# scard_serial.net
KiCad netlist of a schematic drawn in EAGLE
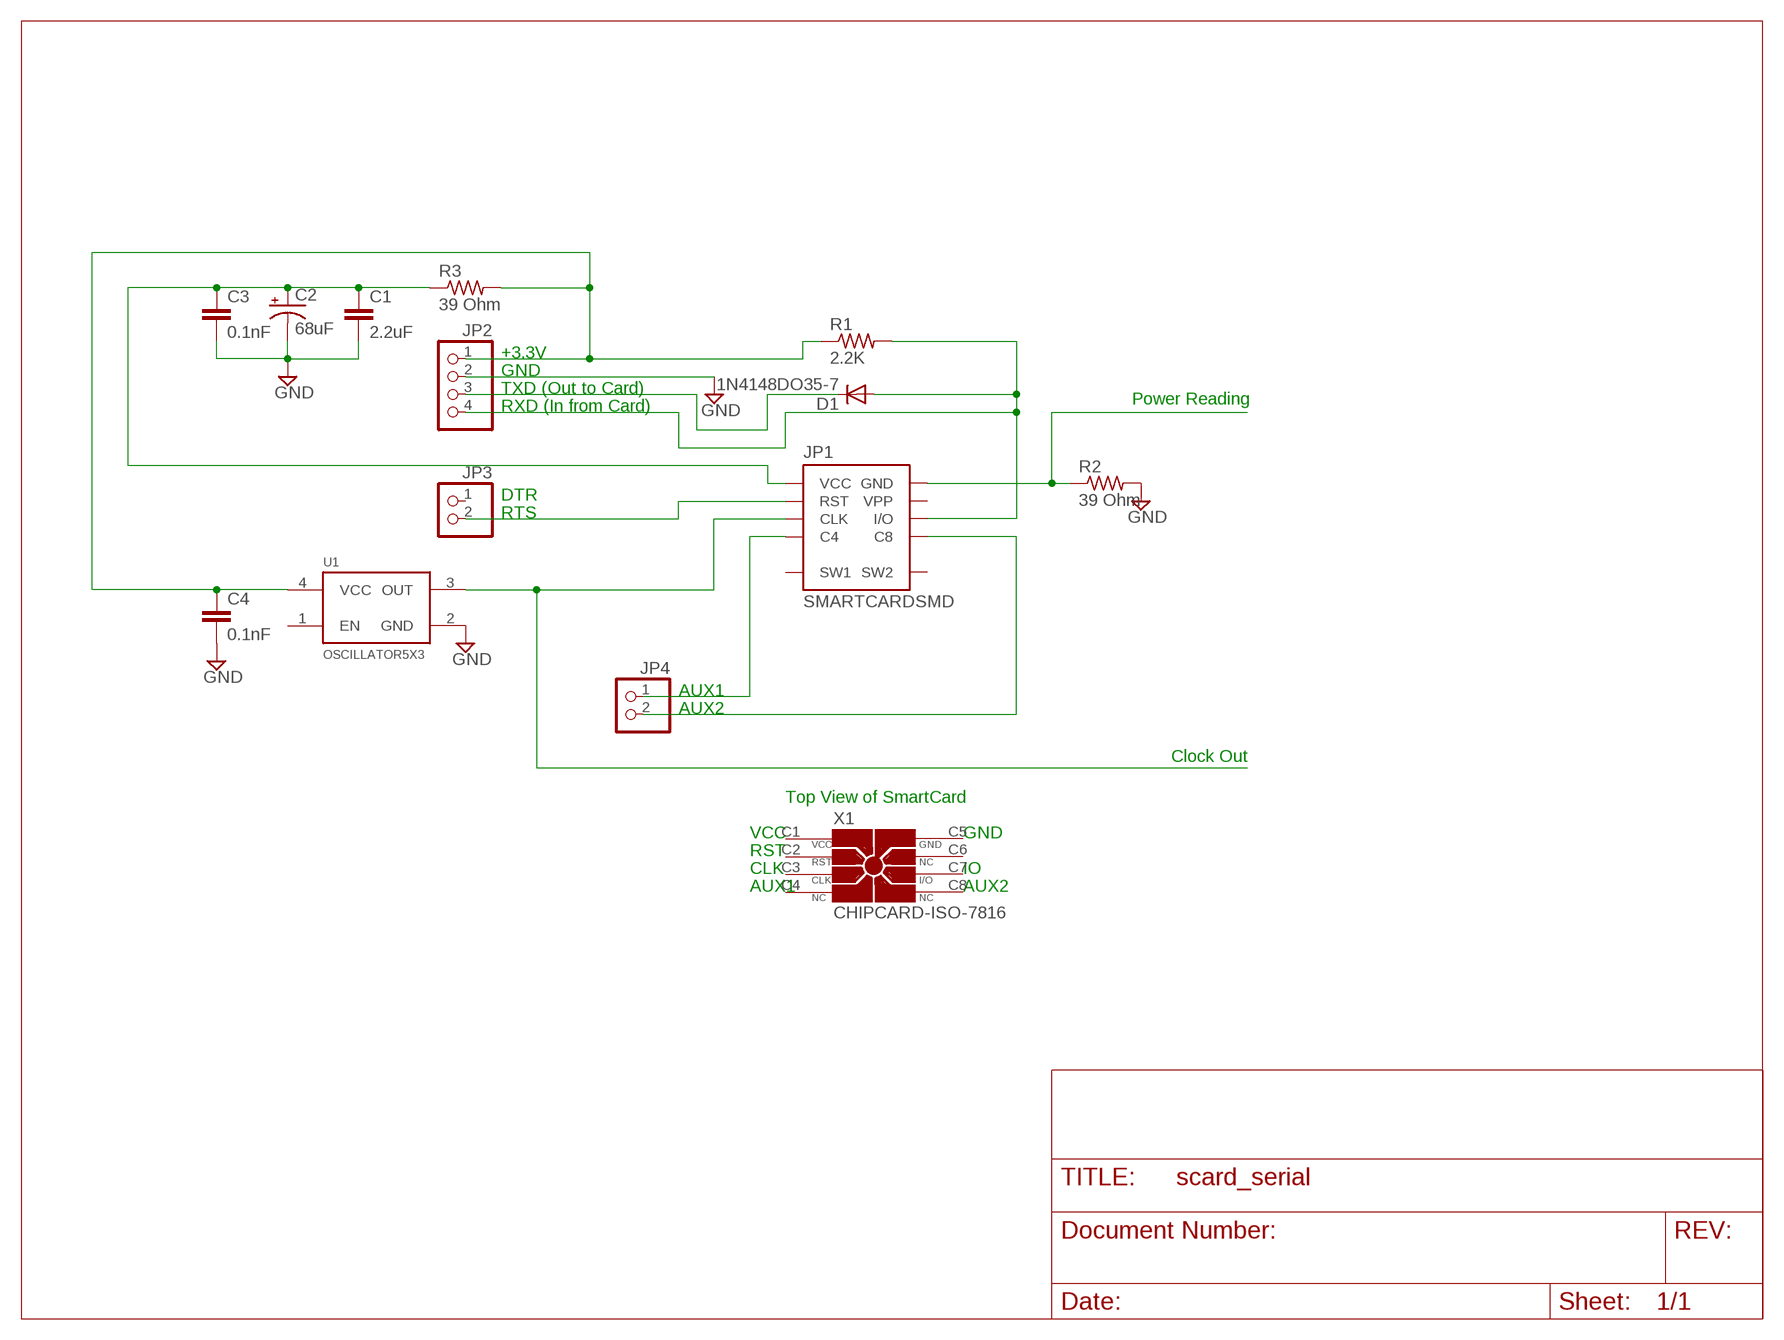
[diagram p0: schematic, sheet 1]

(export (version "E")
  (design (tool "Eeschema 10.0.6"))
  (components
    (comp (ref "C1")
      (value "2.2uF")
      (footprint "eagle-import:C0805")
      (libsource (lib "eagle-import") (part "C-EUC0805"))
    )
    (comp (ref "C2")
      (value "68uF")
      (footprint "eagle-import:139CLL-2W")
      (libsource (lib "eagle-import") (part "CPOL-US139CLL-2W"))
    )
    (comp (ref "C3")
      (value "0.1nF")
      (footprint "eagle-import:C0805")
      (libsource (lib "eagle-import") (part "C-EUC0805"))
    )
    (comp (ref "C4")
      (value "0.1nF")
      (footprint "eagle-import:C0805")
      (libsource (lib "eagle-import") (part "C-EUC0805"))
    )
    (comp (ref "D1")
      (value "1N4148DO35-7")
      (footprint "eagle-import:DO35-7")
      (libsource (lib "eagle-import") (part "1N4148DO35-7"))
    )
    (comp (ref "JP1")
      (value "SMARTCARDSMD")
      (footprint "eagle-import:SMARTCARD")
      (libsource (lib "eagle-import") (part "SMARTCARDSMD"))
    )
    (comp (ref "JP2")
      (value "PINHD-1X4/90")
      (footprint "eagle-import:1X04_90")
      (libsource (lib "eagle-import") (part "PINHD-1X4/90"))
    )
    (comp (ref "JP3")
      (value "PINHD-1X2/90")
      (footprint "eagle-import:1X02_90")
      (libsource (lib "eagle-import") (part "PINHD-1X2/90"))
    )
    (comp (ref "JP4")
      (value "PINHD-1X2/90")
      (footprint "eagle-import:1X02_90")
      (libsource (lib "eagle-import") (part "PINHD-1X2/90"))
    )
    (comp (ref "R1")
      (value "2.2K")
      (footprint "eagle-import:M0805")
      (libsource (lib "eagle-import") (part "R-US_M0805"))
    )
    (comp (ref "R2")
      (value "39 Ohm")
      (footprint "eagle-import:M0805")
      (libsource (lib "eagle-import") (part "R-US_M0805"))
    )
    (comp (ref "R3")
      (value "39 Ohm")
      (footprint "eagle-import:M0805")
      (libsource (lib "eagle-import") (part "R-US_M0805"))
    )
    (comp (ref "U1")
      (value "OSCILLATOR5X3")
      (footprint "eagle-import:CRYSTAL-SMD-5X3")
      (libsource (lib "eagle-import") (part "OSCILLATOR5X3"))
    )
    (comp (ref "X1")
      (value "CHIPCARD-ISO-7816")
      (footprint "eagle-import:ISO7816")
      (libsource (lib "eagle-import") (part "CHIPCARD-ISO-7816"))
    )
  )
  (nets
    (net (code "1") (name "GND") (class "Default")
      (node (ref "C1") (pin "2") (pinfunction "2_2") (pintype "passive"))
      (node (ref "C2") (pin "-") (pinfunction "-_-") (pintype "passive"))
      (node (ref "C3") (pin "2") (pinfunction "2_2") (pintype "passive"))
      (node (ref "C4") (pin "2") (pinfunction "2_2") (pintype "passive"))
      (node (ref "JP2") (pin "2") (pinfunction "2_2") (pintype "passive"))
      (node (ref "R2") (pin "2") (pinfunction "2_2") (pintype "passive"))
      (node (ref "U1") (pin "2") (pinfunction "GND_2") (pintype "bidirectional"))
    )
    (net (code "2") (name "Net-(D1-PadC)") (class "Default")
      (node (ref "D1") (pin "C") (pinfunction "C_C") (pintype "passive"))
      (node (ref "JP2") (pin "3") (pinfunction "3_3") (pintype "passive"))
    )
    (net (code "3") (name "Net-(JP1-CLK)") (class "Default")
      (node (ref "JP1") (pin "C3") (pinfunction "CLK_C3") (pintype "bidirectional"))
      (node (ref "U1") (pin "3") (pinfunction "OUT_3") (pintype "bidirectional"))
    )
    (net (code "4") (name "Net-(JP1-GND)") (class "Default")
      (node (ref "JP1") (pin "C5") (pinfunction "GND_C5") (pintype "bidirectional"))
      (node (ref "R2") (pin "1") (pinfunction "1_1") (pintype "passive"))
    )
    (net (code "5") (name "Net-(JP1-I{slash}O)") (class "Default")
      (node (ref "D1") (pin "A") (pinfunction "A_A") (pintype "passive"))
      (node (ref "JP1") (pin "C7") (pinfunction "I/O_C7") (pintype "bidirectional"))
      (node (ref "JP2") (pin "4") (pinfunction "4_4") (pintype "passive"))
      (node (ref "R1") (pin "2") (pinfunction "2_2") (pintype "passive"))
    )
    (net (code "6") (name "Net-(JP1-PadC4)") (class "Default")
      (node (ref "JP1") (pin "C4") (pinfunction "C4_C4") (pintype "bidirectional"))
      (node (ref "JP4") (pin "1") (pinfunction "1_1") (pintype "passive"))
    )
    (net (code "7") (name "Net-(JP1-PadC8)") (class "Default")
      (node (ref "JP1") (pin "C8") (pinfunction "C8_C8") (pintype "bidirectional"))
      (node (ref "JP4") (pin "2") (pinfunction "2_2") (pintype "passive"))
    )
    (net (code "8") (name "Net-(JP1-RST)") (class "Default")
      (node (ref "JP1") (pin "C2") (pinfunction "RST_C2") (pintype "bidirectional"))
      (node (ref "JP3") (pin "2") (pinfunction "2_2") (pintype "passive"))
    )
    (net (code "9") (name "Net-(JP1-VCC)") (class "Default")
      (node (ref "C1") (pin "1") (pinfunction "1_1") (pintype "passive"))
      (node (ref "C2") (pin "+") (pinfunction "+_+") (pintype "passive"))
      (node (ref "C3") (pin "1") (pinfunction "1_1") (pintype "passive"))
      (node (ref "JP1") (pin "C1") (pinfunction "VCC_C1") (pintype "bidirectional"))
      (node (ref "R3") (pin "1") (pinfunction "1_1") (pintype "passive"))
    )
    (net (code "10") (name "Net-(U1-VCC)") (class "Default")
      (node (ref "C4") (pin "1") (pinfunction "1_1") (pintype "passive"))
      (node (ref "JP2") (pin "1") (pinfunction "1_1") (pintype "passive"))
      (node (ref "R1") (pin "1") (pinfunction "1_1") (pintype "passive"))
      (node (ref "R3") (pin "2") (pinfunction "2_2") (pintype "passive"))
      (node (ref "U1") (pin "4") (pinfunction "VCC_4") (pintype "bidirectional"))
    )
    (net (code "11") (name "unconnected-(JP1-SW1-PadP1)") (class "Default")
      (node (ref "JP1") (pin "P1") (pinfunction "SW1_P1") (pintype "bidirectional"))
    )
    (net (code "12") (name "unconnected-(JP1-SW2-PadP2)") (class "Default")
      (node (ref "JP1") (pin "P2") (pinfunction "SW2_P2") (pintype "bidirectional"))
    )
    (net (code "13") (name "unconnected-(JP1-VPP-PadC6)") (class "Default")
      (node (ref "JP1") (pin "C6") (pinfunction "VPP_C6") (pintype "bidirectional"))
    )
    (net (code "14") (name "unconnected-(JP3-Pad1)") (class "Default")
      (node (ref "JP3") (pin "1") (pinfunction "1_1") (pintype "passive"))
    )
    (net (code "15") (name "unconnected-(U1-EN-Pad1)") (class "Default")
      (node (ref "U1") (pin "1") (pinfunction "EN_1") (pintype "bidirectional"))
    )
    (net (code "16") (name "unconnected-(X1-CLK-PadC3)") (class "Default")
      (node (ref "X1") (pin "C3") (pinfunction "CLK_C3") (pintype "passive"))
    )
    (net (code "17") (name "unconnected-(X1-GND-PadC5)") (class "Default")
      (node (ref "X1") (pin "C5") (pinfunction "GND_C5") (pintype "passive"))
    )
    (net (code "18") (name "unconnected-(X1-I{slash}O-PadC7)") (class "Default")
      (node (ref "X1") (pin "C7") (pinfunction "I/O_C7") (pintype "passive"))
    )
    (net (code "19") (name "unconnected-(X1-NC-PadC4)") (class "Default")
      (node (ref "X1") (pin "C4") (pinfunction "NC_C4") (pintype "passive"))
    )
    (net (code "20") (name "unconnected-(X1-NC-PadC6)") (class "Default")
      (node (ref "X1") (pin "C6") (pinfunction "NC_C6") (pintype "passive"))
    )
    (net (code "21") (name "unconnected-(X1-NC-PadC8)") (class "Default")
      (node (ref "X1") (pin "C8") (pinfunction "NC_C8") (pintype "passive"))
    )
    (net (code "22") (name "unconnected-(X1-RST-PadC2)") (class "Default")
      (node (ref "X1") (pin "C2") (pinfunction "RST_C2") (pintype "passive"))
    )
    (net (code "23") (name "unconnected-(X1-VCC-PadC1)") (class "Default")
      (node (ref "X1") (pin "C1") (pinfunction "VCC_C1") (pintype "passive"))
    )
  )
)
